# Adafruit_Grayscale_1_5-inch_128x128_OLED.net
KiCad netlist of a schematic drawn in EAGLE
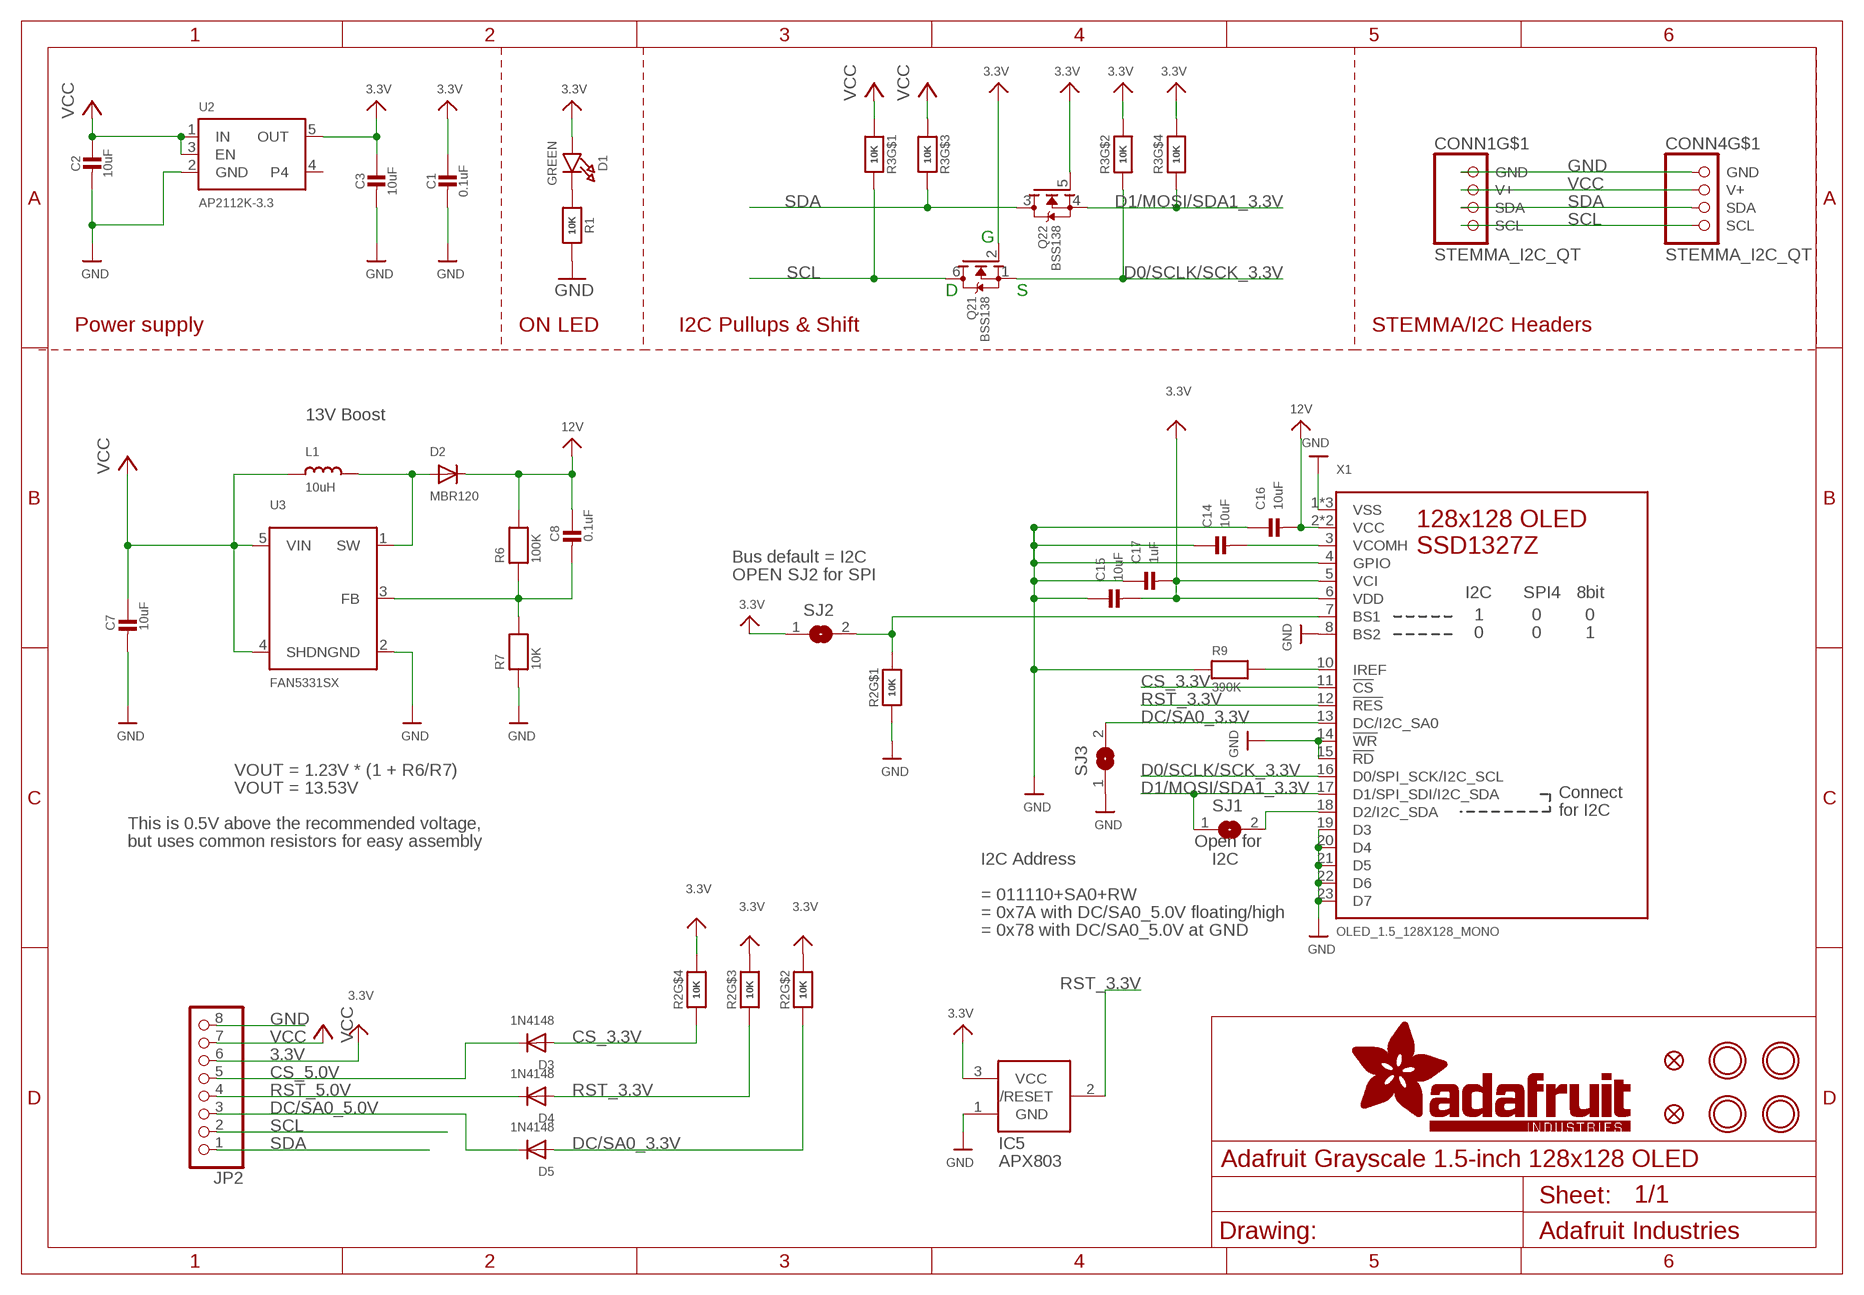
[diagram p0: schematic, sheet 1]

(export (version "E")
  (design (tool "Eeschema 10.0.6"))
  (components
    (comp (ref "C1")
      (value "0.1uF")
      (footprint "eagle-import:0603-NO")
      (libsource (lib "eagle-import") (part "CAP_CERAMIC0603_NO"))
    )
    (comp (ref "C2")
      (value "10uF")
      (footprint "eagle-import:0805-NO")
      (libsource (lib "eagle-import") (part "CAP_CERAMIC0805-NOOUTLINE"))
    )
    (comp (ref "C3")
      (value "10uF")
      (footprint "eagle-import:0805-NO")
      (libsource (lib "eagle-import") (part "CAP_CERAMIC0805-NOOUTLINE"))
    )
    (comp (ref "C7")
      (value "10uF")
      (footprint "eagle-import:0805-NO")
      (libsource (lib "eagle-import") (part "CAP_CERAMIC0805-NOOUTLINE"))
    )
    (comp (ref "C8")
      (value "0.1uF")
      (footprint "eagle-import:0603-NO")
      (libsource (lib "eagle-import") (part "CAP_CERAMIC0603_NO"))
    )
    (comp (ref "C14")
      (value "10uF")
      (footprint "eagle-import:0805-NO")
      (libsource (lib "eagle-import") (part "CAP_CERAMIC0805-NOOUTLINE"))
    )
    (comp (ref "C15")
      (value "10uF")
      (footprint "eagle-import:0805-NO")
      (libsource (lib "eagle-import") (part "CAP_CERAMIC0805-NOOUTLINE"))
    )
    (comp (ref "C16")
      (value "10uF")
      (footprint "eagle-import:0805-NO")
      (libsource (lib "eagle-import") (part "CAP_CERAMIC0805-NOOUTLINE"))
    )
    (comp (ref "C17")
      (value "1uF")
      (footprint "eagle-import:0603-NO")
      (libsource (lib "eagle-import") (part "CAP_CERAMIC0603_NO"))
    )
    (comp (ref "CONN1")
      (value "STEMMA_I2C_QT")
      (footprint "eagle-import:JST_SH4")
      (libsource (lib "eagle-import") (part "STEMMA_I2C_QT"))
    )
    (comp (ref "CONN4")
      (value "STEMMA_I2C_QT")
      (footprint "eagle-import:JST_SH4")
      (libsource (lib "eagle-import") (part "STEMMA_I2C_QT"))
    )
    (comp (ref "D1")
      (value "GREEN")
      (footprint "eagle-import:CHIPLED_0603_NOOUTLINE")
      (libsource (lib "eagle-import") (part "LED0603_NOOUTLINE"))
    )
    (comp (ref "D2")
      (value "MBR120")
      (footprint "eagle-import:SOD-123")
      (libsource (lib "eagle-import") (part "DIODESOD-123"))
    )
    (comp (ref "D3")
      (value "1N4148")
      (footprint "eagle-import:SOD-323")
      (libsource (lib "eagle-import") (part "DIODESOD-323"))
    )
    (comp (ref "D4")
      (value "1N4148")
      (footprint "eagle-import:SOD-323")
      (libsource (lib "eagle-import") (part "DIODESOD-323"))
    )
    (comp (ref "D5")
      (value "1N4148")
      (footprint "eagle-import:SOD-323")
      (libsource (lib "eagle-import") (part "DIODESOD-323"))
    )
    (comp (ref "FID3")
      (value "FIDUCIAL_1MM")
      (footprint "eagle-import:FIDUCIAL_1MM")
      (libsource (lib "eagle-import") (part "FIDUCIAL_1MM"))
    )
    (comp (ref "FID4")
      (value "FIDUCIAL_1MM")
      (footprint "eagle-import:FIDUCIAL_1MM")
      (libsource (lib "eagle-import") (part "FIDUCIAL_1MM"))
    )
    (comp (ref "IC5")
      (value "APX803")
      (footprint "eagle-import:SOT23")
      (libsource (lib "eagle-import") (part "AXP083-SAG"))
    )
    (comp (ref "JP2")
      (value "HEADER-1X870MIL")
      (footprint "eagle-import:1X08_ROUND_70")
      (libsource (lib "eagle-import") (part "HEADER-1X870MIL"))
    )
    (comp (ref "L1")
      (value "10uH")
      (footprint "eagle-import:INDUCTOR_1007")
      (libsource (lib "eagle-import") (part "INDUCTOR"))
    )
    (comp (ref "Q2")
      (value "BSS138")
      (footprint "eagle-import:SOT363")
      (libsource (lib "eagle-import") (part "MOSFET-N_DUAL"))
    )
    (comp (ref "R1")
      (value "10K")
      (footprint "eagle-import:0603-NO")
      (libsource (lib "eagle-import") (part "RESISTOR_0603_NOOUT"))
    )
    (comp (ref "R2")
      (value "10K")
      (footprint "eagle-import:RESPACK_4X0603")
      (libsource (lib "eagle-import") (part "RESISTOR_4PACK"))
    )
    (comp (ref "R3")
      (value "10K")
      (footprint "eagle-import:RESPACK_4X0603")
      (libsource (lib "eagle-import") (part "RESISTOR_4PACK"))
    )
    (comp (ref "R6")
      (value "100K")
      (footprint "eagle-import:0603-NO")
      (libsource (lib "eagle-import") (part "RESISTOR_0603_NOOUT"))
    )
    (comp (ref "R7")
      (value "10K")
      (footprint "eagle-import:0603-NO")
      (libsource (lib "eagle-import") (part "RESISTOR_0603_NOOUT"))
    )
    (comp (ref "R9")
      (value "390K")
      (footprint "eagle-import:0603-NO")
      (libsource (lib "eagle-import") (part "RESISTOR_0603_NOOUT"))
    )
    (comp (ref "SJ1")
      (value "SOLDERJUMPERCLOSED")
      (footprint "eagle-import:SOLDERJUMPER_CLOSEDWIRE")
      (libsource (lib "eagle-import") (part "SOLDERJUMPERCLOSED"))
    )
    (comp (ref "SJ2")
      (value "SOLDERJUMPERCLOSED")
      (footprint "eagle-import:SOLDERJUMPER_CLOSEDWIRE")
      (libsource (lib "eagle-import") (part "SOLDERJUMPERCLOSED"))
    )
    (comp (ref "SJ3")
      (value "SOLDERJUMPER")
      (footprint "eagle-import:SOLDERJUMPER_ARROW_NOPASTE")
      (libsource (lib "eagle-import") (part "SOLDERJUMPER"))
    )
    (comp (ref "U$1")
      (value "MOUNTINGHOLE2.5")
      (footprint "eagle-import:MOUNTINGHOLE_2.5_PLATED")
      (libsource (lib "eagle-import") (part "MOUNTINGHOLE2.5"))
    )
    (comp (ref "U$17")
      (value "MOUNTINGHOLE2.5")
      (footprint "eagle-import:MOUNTINGHOLE_2.5_PLATED")
      (libsource (lib "eagle-import") (part "MOUNTINGHOLE2.5"))
    )
    (comp (ref "U$19")
      (value "MOUNTINGHOLE2.5")
      (footprint "eagle-import:MOUNTINGHOLE_2.5_PLATED")
      (libsource (lib "eagle-import") (part "MOUNTINGHOLE2.5"))
    )
    (comp (ref "U$21")
      (value "MOUNTINGHOLE2.5")
      (footprint "eagle-import:MOUNTINGHOLE_2.5_PLATED")
      (libsource (lib "eagle-import") (part "MOUNTINGHOLE2.5"))
    )
    (comp (ref "U2")
      (value "AP2112K-3.3")
      (footprint "eagle-import:SOT23-5")
      (libsource (lib "eagle-import") (part "VREG_SOT23-5"))
    )
    (comp (ref "U3")
      (value "FAN5331SX")
      (footprint "eagle-import:SOT23-5@1")
      (libsource (lib "eagle-import") (part "FAN5331"))
    )
    (comp (ref "X1")
      (value "OLED_1.5_128X128_MONO")
      (footprint "eagle-import:OLED_1.5IN_128X128MONO")
      (libsource (lib "eagle-import") (part "OLED_1.5_128X128_MONO"))
    )
  )
  (nets
    (net (code "1") (name "/CS_3.3V") (class "Default")
      (node (ref "D3") (pin "A") (pinfunction "A_A") (pintype "passive"))
      (node (ref "R2") (pin "4") (pinfunction "1_4") (pintype "passive"))
      (node (ref "X1") (pin "11") (pinfunction "~{CS}_11") (pintype "input"))
    )
    (net (code "2") (name "/CS_5.0V") (class "Default")
      (node (ref "D3") (pin "C") (pinfunction "C_C") (pintype "passive"))
      (node (ref "JP2") (pin "5") (pinfunction "5_5") (pintype "passive"))
    )
    (net (code "3") (name "/D0{slash}SCLK{slash}SCK_3.3V") (class "Default")
      (node (ref "Q2") (pin "1") (pinfunction "S_1") (pintype "bidirectional"))
      (node (ref "R3") (pin "7") (pinfunction "2_7") (pintype "passive"))
      (node (ref "X1") (pin "16") (pinfunction "D0/SPI_SCK/I2C_SCL_16") (pintype "bidirectional"))
    )
    (net (code "4") (name "/D1{slash}MOSI{slash}SDA1_3.3V") (class "Default")
      (node (ref "Q2") (pin "4") (pinfunction "S_4") (pintype "bidirectional"))
      (node (ref "R3") (pin "5") (pinfunction "2_5") (pintype "passive"))
      (node (ref "SJ1") (pin "1") (pinfunction "1_1") (pintype "passive"))
      (node (ref "X1") (pin "17") (pinfunction "D1/SPI_SDI/I2C_SDA_17") (pintype "bidirectional"))
    )
    (net (code "5") (name "/DC{slash}SA0_3.3V") (class "Default")
      (node (ref "D5") (pin "A") (pinfunction "A_A") (pintype "passive"))
      (node (ref "R2") (pin "2") (pinfunction "1_2") (pintype "passive"))
      (node (ref "SJ3") (pin "2") (pinfunction "2_2") (pintype "passive"))
      (node (ref "X1") (pin "13") (pinfunction "DC/I2C_SA0_13") (pintype "input"))
    )
    (net (code "6") (name "/DC{slash}SA0_5.0V") (class "Default")
      (node (ref "D5") (pin "C") (pinfunction "C_C") (pintype "passive"))
      (node (ref "JP2") (pin "3") (pinfunction "3_3") (pintype "passive"))
    )
    (net (code "7") (name "/RST_3.3V") (class "Default")
      (node (ref "D4") (pin "A") (pinfunction "A_A") (pintype "passive"))
      (node (ref "IC5") (pin "2") (pinfunction "/RESET_2") (pintype "output"))
      (node (ref "R2") (pin "3") (pinfunction "1_3") (pintype "passive"))
      (node (ref "X1") (pin "12") (pinfunction "~{RES}_12") (pintype "input"))
    )
    (net (code "8") (name "/RST_5.0V") (class "Default")
      (node (ref "D4") (pin "C") (pinfunction "C_C") (pintype "passive"))
      (node (ref "JP2") (pin "4") (pinfunction "4_4") (pintype "passive"))
    )
    (net (code "9") (name "/SCL") (class "Default")
      (node (ref "CONN1") (pin "4") (pinfunction "SCL_4") (pintype "passive"))
      (node (ref "CONN4") (pin "4") (pinfunction "SCL_4") (pintype "passive"))
      (node (ref "JP2") (pin "2") (pinfunction "2_2") (pintype "passive"))
      (node (ref "Q2") (pin "6") (pinfunction "D_6") (pintype "bidirectional"))
      (node (ref "R3") (pin "8") (pinfunction "2_8") (pintype "passive"))
    )
    (net (code "10") (name "/SDA") (class "Default")
      (node (ref "CONN1") (pin "3") (pinfunction "SDA_3") (pintype "passive"))
      (node (ref "CONN4") (pin "3") (pinfunction "SDA_3") (pintype "passive"))
      (node (ref "JP2") (pin "1") (pinfunction "1_1") (pintype "passive"))
      (node (ref "Q2") (pin "3") (pinfunction "D_3") (pintype "bidirectional"))
      (node (ref "R3") (pin "6") (pinfunction "2_6") (pintype "passive"))
    )
    (net (code "11") (name "3.3V") (class "Default")
      (node (ref "C1") (pin "1") (pinfunction "1_1") (pintype "passive"))
      (node (ref "C15") (pin "2") (pinfunction "2_2") (pintype "passive"))
      (node (ref "C17") (pin "2") (pinfunction "2_2") (pintype "passive"))
      (node (ref "C3") (pin "1") (pinfunction "1_1") (pintype "passive"))
      (node (ref "D1") (pin "A") (pinfunction "A_A") (pintype "passive"))
      (node (ref "IC5") (pin "3") (pinfunction "VCC_3") (pintype "power_in"))
      (node (ref "JP2") (pin "6") (pinfunction "6_6") (pintype "passive"))
      (node (ref "Q2") (pin "2") (pinfunction "G_2") (pintype "bidirectional"))
      (node (ref "Q2") (pin "5") (pinfunction "G_5") (pintype "bidirectional"))
      (node (ref "R2") (pin "5") (pinfunction "2_5") (pintype "passive"))
      (node (ref "R2") (pin "6") (pinfunction "2_6") (pintype "passive"))
      (node (ref "R2") (pin "7") (pinfunction "2_7") (pintype "passive"))
      (node (ref "R3") (pin "2") (pinfunction "1_2") (pintype "passive"))
      (node (ref "R3") (pin "4") (pinfunction "1_4") (pintype "passive"))
      (node (ref "SJ2") (pin "1") (pinfunction "1_1") (pintype "passive"))
      (node (ref "U2") (pin "5") (pinfunction "OUT_5") (pintype "power_in"))
      (node (ref "X1") (pin "5") (pinfunction "VCI_5") (pintype "power_in"))
      (node (ref "X1") (pin "6") (pinfunction "VDD_6") (pintype "power_in"))
    )
    (net (code "12") (name "12V") (class "Default")
      (node (ref "C16") (pin "2") (pinfunction "2_2") (pintype "passive"))
      (node (ref "C8") (pin "1") (pinfunction "1_1") (pintype "passive"))
      (node (ref "D2") (pin "C") (pinfunction "C_C") (pintype "passive"))
      (node (ref "R6") (pin "2") (pinfunction "2_2") (pintype "passive"))
      (node (ref "X1") (pin "2") (pinfunction "VCC_2") (pintype "power_in"))
      (node (ref "X1") (pin "24") (pinfunction "VCC_24") (pintype "power_in"))
    )
    (net (code "13") (name "GND") (class "Default")
      (node (ref "C1") (pin "2") (pinfunction "2_2") (pintype "passive"))
      (node (ref "C14") (pin "1") (pinfunction "1_1") (pintype "passive"))
      (node (ref "C15") (pin "1") (pinfunction "1_1") (pintype "passive"))
      (node (ref "C16") (pin "1") (pinfunction "1_1") (pintype "passive"))
      (node (ref "C17") (pin "1") (pinfunction "1_1") (pintype "passive"))
      (node (ref "C2") (pin "2") (pinfunction "2_2") (pintype "passive"))
      (node (ref "C3") (pin "2") (pinfunction "2_2") (pintype "passive"))
      (node (ref "C7") (pin "2") (pinfunction "2_2") (pintype "passive"))
      (node (ref "CONN1") (pin "1") (pinfunction "GND_1") (pintype "passive"))
      (node (ref "CONN4") (pin "1") (pinfunction "GND_1") (pintype "passive"))
      (node (ref "IC5") (pin "1") (pinfunction "GND_1") (pintype "power_in"))
      (node (ref "JP2") (pin "8") (pinfunction "8_8") (pintype "passive"))
      (node (ref "R1") (pin "2") (pinfunction "2_2") (pintype "passive"))
      (node (ref "R2") (pin "1") (pinfunction "1_1") (pintype "passive"))
      (node (ref "R7") (pin "1") (pinfunction "1_1") (pintype "passive"))
      (node (ref "R9") (pin "1") (pinfunction "1_1") (pintype "passive"))
      (node (ref "SJ3") (pin "1") (pinfunction "1_1") (pintype "passive"))
      (node (ref "U2") (pin "2") (pinfunction "GND_2") (pintype "power_in"))
      (node (ref "U3") (pin "2") (pinfunction "GND_2") (pintype "bidirectional"))
      (node (ref "X1") (pin "1") (pinfunction "VSS_1") (pintype "power_in"))
      (node (ref "X1") (pin "14") (pinfunction "~{WR}_14") (pintype "input"))
      (node (ref "X1") (pin "15") (pinfunction "~{RD}_15") (pintype "input"))
      (node (ref "X1") (pin "19") (pinfunction "D3_19") (pintype "bidirectional"))
      (node (ref "X1") (pin "20") (pinfunction "D4_20") (pintype "bidirectional"))
      (node (ref "X1") (pin "21") (pinfunction "D5_21") (pintype "bidirectional"))
      (node (ref "X1") (pin "22") (pinfunction "D6_22") (pintype "bidirectional"))
      (node (ref "X1") (pin "23") (pinfunction "D7_23") (pintype "bidirectional"))
      (node (ref "X1") (pin "25") (pinfunction "VSS_25") (pintype "power_in"))
      (node (ref "X1") (pin "4") (pinfunction "GPIO_4") (pintype "input"))
      (node (ref "X1") (pin "8") (pinfunction "BS2_8") (pintype "input"))
      (node (ref "X1") (pin "9") (pinfunction "VSS_9") (pintype "power_in"))
    )
    (net (code "14") (name "Net-(D1-PadC)") (class "Default")
      (node (ref "D1") (pin "C") (pinfunction "C_C") (pintype "passive"))
      (node (ref "R1") (pin "1") (pinfunction "1_1") (pintype "passive"))
    )
    (net (code "15") (name "Net-(L1-2)") (class "Default")
      (node (ref "D2") (pin "A") (pinfunction "A_A") (pintype "passive"))
      (node (ref "L1") (pin "P$2") (pinfunction "2_P$2") (pintype "passive"))
      (node (ref "U3") (pin "1") (pinfunction "SW_1") (pintype "bidirectional"))
    )
    (net (code "16") (name "Net-(R2A-2)") (class "Default")
      (node (ref "R2") (pin "8") (pinfunction "2_8") (pintype "passive"))
      (node (ref "SJ2") (pin "2") (pinfunction "2_2") (pintype "passive"))
      (node (ref "X1") (pin "7") (pinfunction "BS1_7") (pintype "input"))
    )
    (net (code "17") (name "Net-(U3-FB)") (class "Default")
      (node (ref "C8") (pin "2") (pinfunction "2_2") (pintype "passive"))
      (node (ref "R6") (pin "1") (pinfunction "1_1") (pintype "passive"))
      (node (ref "R7") (pin "2") (pinfunction "2_2") (pintype "passive"))
      (node (ref "U3") (pin "3") (pinfunction "FB_3") (pintype "bidirectional"))
    )
    (net (code "18") (name "Net-(X1-D2{slash}I2C_SDA)") (class "Default")
      (node (ref "SJ1") (pin "2") (pinfunction "2_2") (pintype "passive"))
      (node (ref "X1") (pin "18") (pinfunction "D2/I2C_SDA_18") (pintype "bidirectional"))
    )
    (net (code "19") (name "Net-(X1-IREF)") (class "Default")
      (node (ref "R9") (pin "2") (pinfunction "2_2") (pintype "passive"))
      (node (ref "X1") (pin "10") (pinfunction "IREF_10") (pintype "input"))
    )
    (net (code "20") (name "Net-(X1-VCOMH)") (class "Default")
      (node (ref "C14") (pin "2") (pinfunction "2_2") (pintype "passive"))
      (node (ref "X1") (pin "3") (pinfunction "VCOMH_3") (pintype "output"))
    )
    (net (code "21") (name "VCC") (class "Default")
      (node (ref "C2") (pin "1") (pinfunction "1_1") (pintype "passive"))
      (node (ref "C7") (pin "1") (pinfunction "1_1") (pintype "passive"))
      (node (ref "CONN1") (pin "2") (pinfunction "V+_2") (pintype "passive"))
      (node (ref "CONN4") (pin "2") (pinfunction "V+_2") (pintype "passive"))
      (node (ref "JP2") (pin "7") (pinfunction "7_7") (pintype "passive"))
      (node (ref "L1") (pin "P$1") (pinfunction "1_P$1") (pintype "passive"))
      (node (ref "R3") (pin "1") (pinfunction "1_1") (pintype "passive"))
      (node (ref "R3") (pin "3") (pinfunction "1_3") (pintype "passive"))
      (node (ref "U2") (pin "1") (pinfunction "IN_1") (pintype "power_in"))
      (node (ref "U2") (pin "3") (pinfunction "EN_3") (pintype "input"))
      (node (ref "U3") (pin "4") (pinfunction "SHDN_4") (pintype "bidirectional"))
      (node (ref "U3") (pin "5") (pinfunction "VIN_5") (pintype "bidirectional"))
    )
    (net (code "22") (name "unconnected-(U2-P4-Pad4)") (class "Default")
      (node (ref "U2") (pin "4") (pinfunction "P4_4") (pintype "bidirectional"))
    )
  )
)
